# design.net
KiCad netlist of a schematic drawn in Altium Designer
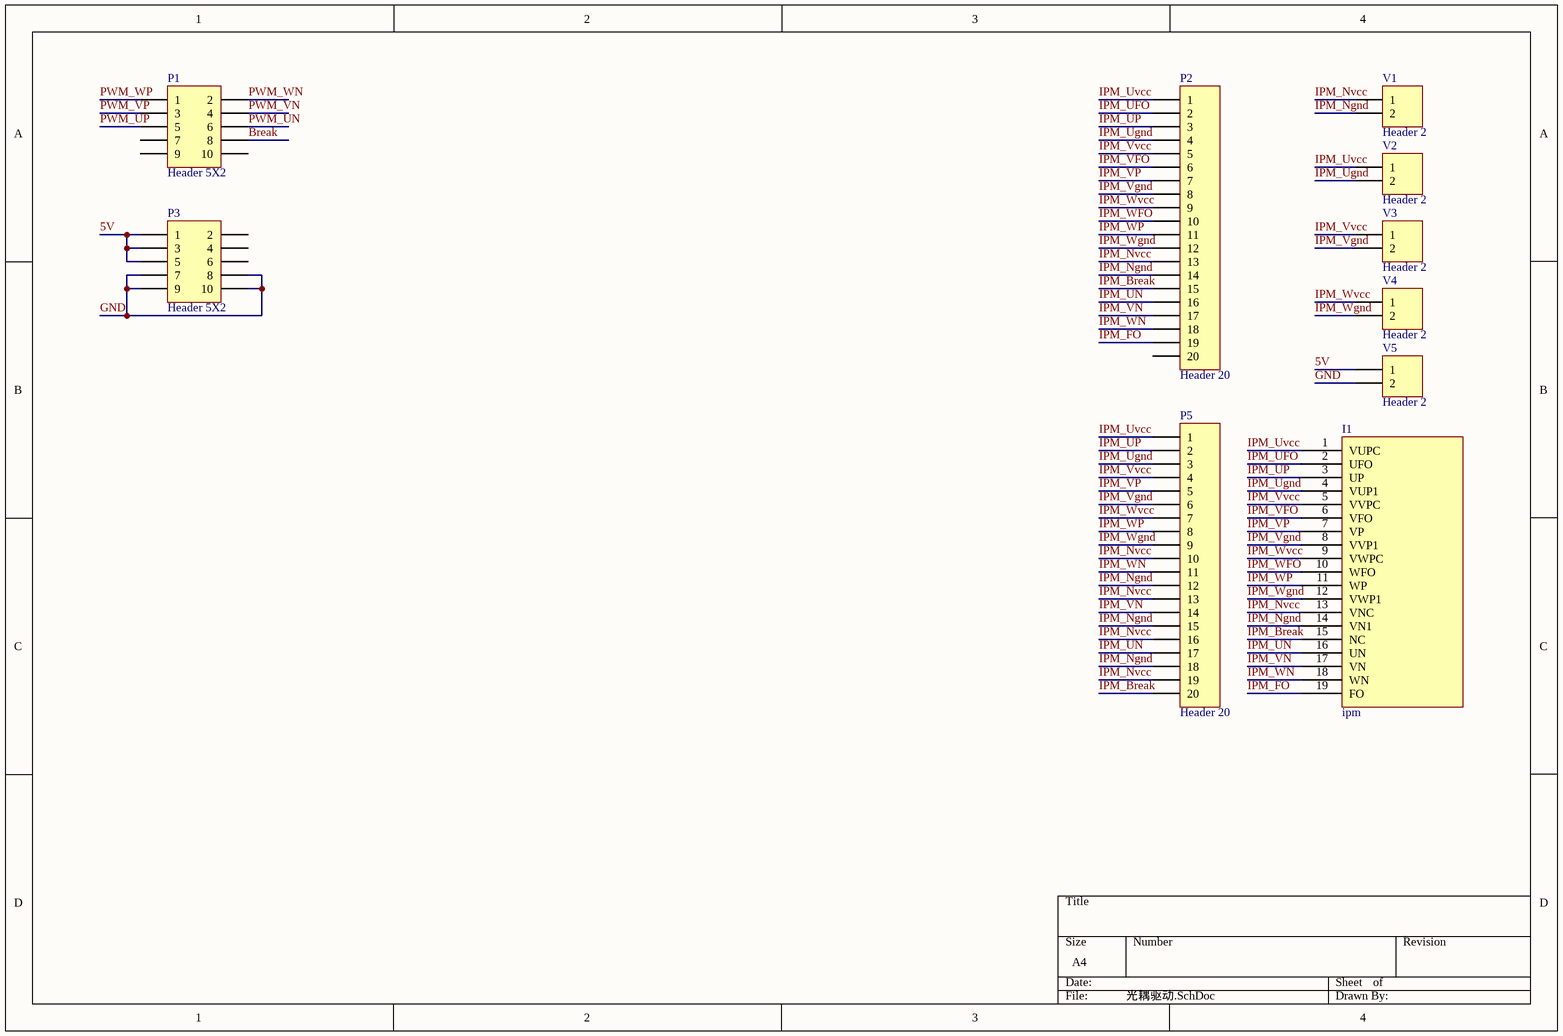
[diagram p0: 光耦驱动.SchDoc]

(export (version "E")
  (design (tool "Eeschema 10.0.6"))
  (components
    (comp (ref "I1") (value "ipm") (footprint "ipm") (libsource (lib "my schematic") (part "ipm")))
    (comp (ref "P1")
      (value "Header 5X2")
      (footprint "HDR2X5")
      (description "Header, 5-Pin, Dual row")
      (fields (field (name "PUBLISHER") "Altium Limited"))
      (libsource (lib "Miscellaneous Connectors") (part "Header 5X2"))
    )
    (comp (ref "P2")
      (value "Header 20")
      (footprint "HDR1X20")
      (description "Header, 20-Pin")
      (fields (field (name "PUBLISHER") "Altium Limited"))
      (libsource (lib "Miscellaneous Connectors") (part "Header 20"))
    )
    (comp (ref "P3")
      (value "Header 5X2")
      (footprint "HDR2X5")
      (description "Header, 5-Pin, Dual row")
      (fields (field (name "PUBLISHER") "Altium Limited"))
      (libsource (lib "Miscellaneous Connectors") (part "Header 5X2"))
    )
    (comp (ref "P5")
      (value "Header 20")
      (footprint "HDR1X20")
      (description "Header, 20-Pin")
      (fields (field (name "PUBLISHER") "Altium Limited"))
      (libsource (lib "Miscellaneous Connectors") (part "Header 20"))
    )
    (comp (ref "V1")
      (value "Header 2")
      (footprint "HDR1X2")
      (description "Header, 2-Pin")
      (fields (field (name "PUBLISHER") "Altium Limited"))
      (libsource (lib "Miscellaneous Connectors") (part "Header 2"))
    )
    (comp (ref "V2")
      (value "Header 2")
      (footprint "HDR1X2")
      (description "Header, 2-Pin")
      (fields (field (name "PUBLISHER") "Altium Limited"))
      (libsource (lib "Miscellaneous Connectors") (part "Header 2"))
    )
    (comp (ref "V3")
      (value "Header 2")
      (footprint "HDR1X2")
      (description "Header, 2-Pin")
      (fields (field (name "PUBLISHER") "Altium Limited"))
      (libsource (lib "Miscellaneous Connectors") (part "Header 2"))
    )
    (comp (ref "V4")
      (value "Header 2")
      (footprint "HDR1X2")
      (description "Header, 2-Pin")
      (fields (field (name "PUBLISHER") "Altium Limited"))
      (libsource (lib "Miscellaneous Connectors") (part "Header 2"))
    )
    (comp (ref "V5")
      (value "Header 2")
      (footprint "HDR1X2")
      (description "Header, 2-Pin")
      (fields (field (name "PUBLISHER") "Altium Limited"))
      (libsource (lib "Miscellaneous Connectors") (part "Header 2"))
    )
  )
  (nets
    (net (code "1") (name "/5V") (class "Default")
      (node (ref "P3") (pin "1") (pinfunction "1_1") (pintype "passive"))
      (node (ref "P3") (pin "3") (pinfunction "3_3") (pintype "passive"))
      (node (ref "P3") (pin "5") (pinfunction "5_5") (pintype "passive"))
      (node (ref "V5") (pin "1") (pinfunction "1_1") (pintype "passive"))
    )
    (net (code "2") (name "/Break") (class "Default")
      (node (ref "P1") (pin "8") (pinfunction "8_8") (pintype "passive"))
    )
    (net (code "3") (name "/GND") (class "Default")
      (node (ref "P3") (pin "10") (pinfunction "10_10") (pintype "passive"))
      (node (ref "P3") (pin "7") (pinfunction "7_7") (pintype "passive"))
      (node (ref "P3") (pin "8") (pinfunction "8_8") (pintype "passive"))
      (node (ref "P3") (pin "9") (pinfunction "9_9") (pintype "passive"))
      (node (ref "V5") (pin "2") (pinfunction "2_2") (pintype "passive"))
    )
    (net (code "4") (name "/IPM_Break") (class "Default")
      (node (ref "I1") (pin "15") (pinfunction "NC_15") (pintype "passive"))
      (node (ref "P2") (pin "15") (pinfunction "15_15") (pintype "passive"))
      (node (ref "P5") (pin "20") (pinfunction "20_20") (pintype "passive"))
    )
    (net (code "5") (name "/IPM_FO") (class "Default")
      (node (ref "I1") (pin "19") (pinfunction "FO_19") (pintype "passive"))
      (node (ref "P2") (pin "19") (pinfunction "19_19") (pintype "passive"))
    )
    (net (code "6") (name "/IPM_Ngnd") (class "Default")
      (node (ref "I1") (pin "14") (pinfunction "VN1_14") (pintype "passive"))
      (node (ref "P2") (pin "14") (pinfunction "14_14") (pintype "passive"))
      (node (ref "P5") (pin "12") (pinfunction "12_12") (pintype "passive"))
      (node (ref "P5") (pin "15") (pinfunction "15_15") (pintype "passive"))
      (node (ref "P5") (pin "18") (pinfunction "18_18") (pintype "passive"))
      (node (ref "V1") (pin "2") (pinfunction "2_2") (pintype "passive"))
    )
    (net (code "7") (name "/IPM_Nvcc") (class "Default")
      (node (ref "I1") (pin "13") (pinfunction "VNC_13") (pintype "passive"))
      (node (ref "P2") (pin "13") (pinfunction "13_13") (pintype "passive"))
      (node (ref "P5") (pin "10") (pinfunction "10_10") (pintype "passive"))
      (node (ref "P5") (pin "13") (pinfunction "13_13") (pintype "passive"))
      (node (ref "P5") (pin "16") (pinfunction "16_16") (pintype "passive"))
      (node (ref "P5") (pin "19") (pinfunction "19_19") (pintype "passive"))
      (node (ref "V1") (pin "1") (pinfunction "1_1") (pintype "passive"))
    )
    (net (code "8") (name "/IPM_UFO") (class "Default")
      (node (ref "I1") (pin "2") (pinfunction "UFO_2") (pintype "passive"))
      (node (ref "P2") (pin "2") (pinfunction "2_2") (pintype "passive"))
    )
    (net (code "9") (name "/IPM_UN") (class "Default")
      (node (ref "I1") (pin "16") (pinfunction "UN_16") (pintype "passive"))
      (node (ref "P2") (pin "16") (pinfunction "16_16") (pintype "passive"))
      (node (ref "P5") (pin "17") (pinfunction "17_17") (pintype "passive"))
    )
    (net (code "10") (name "/IPM_UP") (class "Default")
      (node (ref "I1") (pin "3") (pinfunction "UP_3") (pintype "passive"))
      (node (ref "P2") (pin "3") (pinfunction "3_3") (pintype "passive"))
      (node (ref "P5") (pin "2") (pinfunction "2_2") (pintype "passive"))
    )
    (net (code "11") (name "/IPM_Ugnd") (class "Default")
      (node (ref "I1") (pin "4") (pinfunction "VUP1_4") (pintype "passive"))
      (node (ref "P2") (pin "4") (pinfunction "4_4") (pintype "passive"))
      (node (ref "P5") (pin "3") (pinfunction "3_3") (pintype "passive"))
      (node (ref "V2") (pin "2") (pinfunction "2_2") (pintype "passive"))
    )
    (net (code "12") (name "/IPM_Uvcc") (class "Default")
      (node (ref "I1") (pin "1") (pinfunction "VUPC_1") (pintype "passive"))
      (node (ref "P2") (pin "1") (pinfunction "1_1") (pintype "passive"))
      (node (ref "P5") (pin "1") (pinfunction "1_1") (pintype "passive"))
      (node (ref "V2") (pin "1") (pinfunction "1_1") (pintype "passive"))
    )
    (net (code "13") (name "/IPM_VFO") (class "Default")
      (node (ref "I1") (pin "6") (pinfunction "VFO_6") (pintype "passive"))
      (node (ref "P2") (pin "6") (pinfunction "6_6") (pintype "passive"))
    )
    (net (code "14") (name "/IPM_VN") (class "Default")
      (node (ref "I1") (pin "17") (pinfunction "VN_17") (pintype "passive"))
      (node (ref "P2") (pin "17") (pinfunction "17_17") (pintype "passive"))
      (node (ref "P5") (pin "14") (pinfunction "14_14") (pintype "passive"))
    )
    (net (code "15") (name "/IPM_VP") (class "Default")
      (node (ref "I1") (pin "7") (pinfunction "VP_7") (pintype "passive"))
      (node (ref "P2") (pin "7") (pinfunction "7_7") (pintype "passive"))
      (node (ref "P5") (pin "5") (pinfunction "5_5") (pintype "passive"))
    )
    (net (code "16") (name "/IPM_Vgnd") (class "Default")
      (node (ref "I1") (pin "8") (pinfunction "VVP1_8") (pintype "passive"))
      (node (ref "P2") (pin "8") (pinfunction "8_8") (pintype "passive"))
      (node (ref "P5") (pin "6") (pinfunction "6_6") (pintype "passive"))
      (node (ref "V3") (pin "2") (pinfunction "2_2") (pintype "passive"))
    )
    (net (code "17") (name "/IPM_Vvcc") (class "Default")
      (node (ref "I1") (pin "5") (pinfunction "VVPC_5") (pintype "passive"))
      (node (ref "P2") (pin "5") (pinfunction "5_5") (pintype "passive"))
      (node (ref "P5") (pin "4") (pinfunction "4_4") (pintype "passive"))
      (node (ref "V3") (pin "1") (pinfunction "1_1") (pintype "passive"))
    )
    (net (code "18") (name "/IPM_WFO") (class "Default")
      (node (ref "I1") (pin "10") (pinfunction "WFO_10") (pintype "passive"))
      (node (ref "P2") (pin "10") (pinfunction "10_10") (pintype "passive"))
    )
    (net (code "19") (name "/IPM_WN") (class "Default")
      (node (ref "I1") (pin "18") (pinfunction "WN_18") (pintype "passive"))
      (node (ref "P2") (pin "18") (pinfunction "18_18") (pintype "passive"))
      (node (ref "P5") (pin "11") (pinfunction "11_11") (pintype "passive"))
    )
    (net (code "20") (name "/IPM_WP") (class "Default")
      (node (ref "I1") (pin "11") (pinfunction "WP_11") (pintype "passive"))
      (node (ref "P2") (pin "11") (pinfunction "11_11") (pintype "passive"))
      (node (ref "P5") (pin "8") (pinfunction "8_8") (pintype "passive"))
    )
    (net (code "21") (name "/IPM_Wgnd") (class "Default")
      (node (ref "I1") (pin "12") (pinfunction "VWP1_12") (pintype "passive"))
      (node (ref "P2") (pin "12") (pinfunction "12_12") (pintype "passive"))
      (node (ref "P5") (pin "9") (pinfunction "9_9") (pintype "passive"))
      (node (ref "V4") (pin "2") (pinfunction "2_2") (pintype "passive"))
    )
    (net (code "22") (name "/IPM_Wvcc") (class "Default")
      (node (ref "I1") (pin "9") (pinfunction "VWPC_9") (pintype "passive"))
      (node (ref "P2") (pin "9") (pinfunction "9_9") (pintype "passive"))
      (node (ref "P5") (pin "7") (pinfunction "7_7") (pintype "passive"))
      (node (ref "V4") (pin "1") (pinfunction "1_1") (pintype "passive"))
    )
    (net (code "23") (name "/PWM_UN") (class "Default")
      (node (ref "P1") (pin "6") (pinfunction "6_6") (pintype "passive"))
    )
    (net (code "24") (name "/PWM_UP") (class "Default")
      (node (ref "P1") (pin "5") (pinfunction "5_5") (pintype "passive"))
    )
    (net (code "25") (name "/PWM_VN") (class "Default")
      (node (ref "P1") (pin "4") (pinfunction "4_4") (pintype "passive"))
    )
    (net (code "26") (name "/PWM_VP") (class "Default")
      (node (ref "P1") (pin "3") (pinfunction "3_3") (pintype "passive"))
    )
    (net (code "27") (name "/PWM_WN") (class "Default")
      (node (ref "P1") (pin "2") (pinfunction "2_2") (pintype "passive"))
    )
    (net (code "28") (name "/PWM_WP") (class "Default")
      (node (ref "P1") (pin "1") (pinfunction "1_1") (pintype "passive"))
    )
    (net (code "29") (name "unconnected-(P1-Pad7)") (class "Default")
      (node (ref "P1") (pin "7") (pinfunction "7_7") (pintype "passive"))
    )
    (net (code "30") (name "unconnected-(P1-Pad9)") (class "Default")
      (node (ref "P1") (pin "9") (pinfunction "9_9") (pintype "passive"))
    )
    (net (code "31") (name "unconnected-(P1-Pad10)") (class "Default")
      (node (ref "P1") (pin "10") (pinfunction "10_10") (pintype "passive"))
    )
    (net (code "32") (name "unconnected-(P2-Pad20)") (class "Default")
      (node (ref "P2") (pin "20") (pinfunction "20_20") (pintype "passive"))
    )
    (net (code "33") (name "unconnected-(P3-Pad2)") (class "Default")
      (node (ref "P3") (pin "2") (pinfunction "2_2") (pintype "passive"))
    )
    (net (code "34") (name "unconnected-(P3-Pad4)") (class "Default")
      (node (ref "P3") (pin "4") (pinfunction "4_4") (pintype "passive"))
    )
    (net (code "35") (name "unconnected-(P3-Pad6)") (class "Default")
      (node (ref "P3") (pin "6") (pinfunction "6_6") (pintype "passive"))
    )
  )
)
